# Sensor_TCRT5000_board_V_1_0.net
KiCad netlist of a schematic drawn in EAGLE
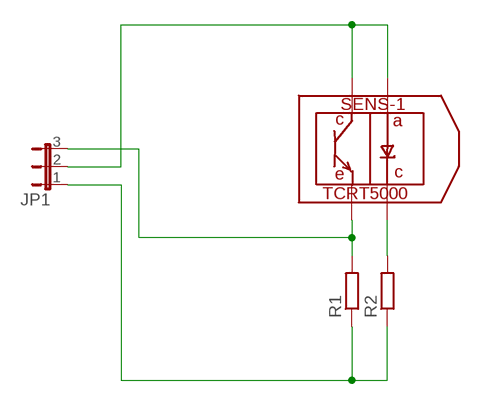
[diagram p0: schematic, sheet 1]

(export (version "E")
  (design (tool "Eeschema 10.0.6"))
  (components
    (comp (ref "JP1")
      (value "JP2E")
      (footprint "eagle-import:JP2")
      (libsource (lib "eagle-import") (part "JP2E"))
    )
    (comp (ref "R1")
      (value "R-EU_0309/10")
      (footprint "eagle-import:0309_10")
      (libsource (lib "eagle-import") (part "R-EU_0309/10"))
    )
    (comp (ref "R2")
      (value "R-EU_0309/10")
      (footprint "eagle-import:0309_10")
      (libsource (lib "eagle-import") (part "R-EU_0309/10"))
    )
    (comp (ref "SENS-1")
      (value "TCRT5000")
      (footprint "eagle-import:5000")
      (libsource (lib "eagle-import") (part "TCRT5000"))
    )
  )
  (nets
    (net (code "1") (name "Net-(JP1-Pad1)") (class "Default")
      (node (ref "JP1") (pin "1") (pinfunction "1_1") (pintype "passive"))
      (node (ref "R1") (pin "1") (pinfunction "1_1") (pintype "passive"))
      (node (ref "R2") (pin "1") (pinfunction "1_1") (pintype "passive"))
    )
    (net (code "2") (name "Net-(JP1-Pad2)") (class "Default")
      (node (ref "JP1") (pin "2") (pinfunction "2_2") (pintype "passive"))
      (node (ref "SENS-1") (pin "P$1") (pinfunction "P$1_P$1") (pintype "passive"))
      (node (ref "SENS-1") (pin "P$3") (pinfunction "P$3_P$3") (pintype "passive"))
    )
    (net (code "3") (name "Net-(JP1-Pad3)") (class "Default")
      (node (ref "JP1") (pin "3") (pinfunction "3_3") (pintype "passive"))
      (node (ref "R1") (pin "2") (pinfunction "2_2") (pintype "passive"))
      (node (ref "SENS-1") (pin "P$2") (pinfunction "P$2_P$2") (pintype "passive"))
    )
    (net (code "4") (name "Net-(R2-Pad2)") (class "Default")
      (node (ref "R2") (pin "2") (pinfunction "2_2") (pintype "passive"))
      (node (ref "SENS-1") (pin "P$4") (pinfunction "P$4_P$4") (pintype "passive"))
    )
  )
)
